# roco1044.net
KiCad netlist of a schematic drawn in EAGLE
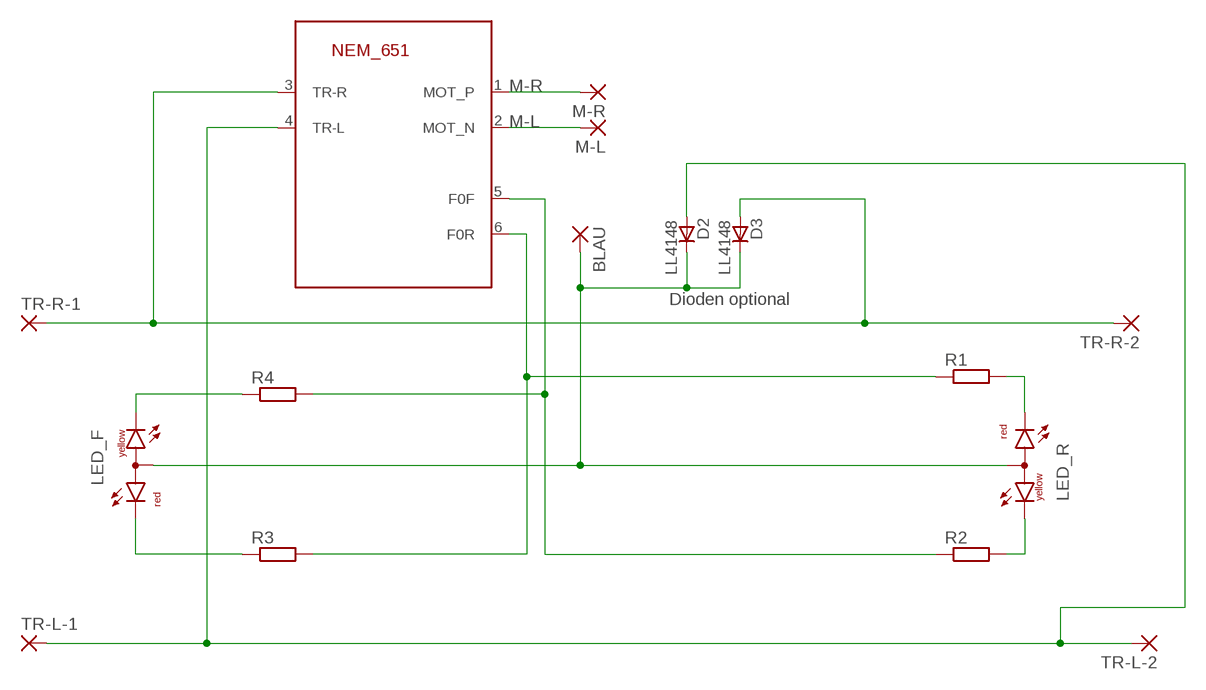
[diagram p0: schematic, sheet 1]

(export (version "E")
  (design (tool "Eeschema 10.0.6"))
  (components
    (comp (ref "651")
      (value "NEM_651-TS")
      (footprint "eagle-import:53047-06")
      (libsource (lib "eagle-import") (part "NEM_651-TS"))
    )
    (comp (ref "BLAU")
      (value "1,6/0,8")
      (footprint "eagle-import:1,6_0,8")
      (libsource (lib "eagle-import") (part "1,6/0,8"))
    )
    (comp (ref "D2")
      (value "LL4148")
      (footprint "eagle-import:SOD80_DO213AA_MINIMELF")
      (libsource (lib "eagle-import") (part "LL4148"))
    )
    (comp (ref "D3")
      (value "LL4148")
      (footprint "eagle-import:SOD80_DO213AA_MINIMELF")
      (libsource (lib "eagle-import") (part "LL4148"))
    )
    (comp (ref "LED_F")
      (value "DUOLED-RY-A")
      (footprint "eagle-import:DUOLED-A-5MM")
      (libsource (lib "eagle-import") (part "DUOLED-RY-A"))
    )
    (comp (ref "LED_R")
      (value "DUOLED-RY-A")
      (footprint "eagle-import:DUOLED-A-5MM")
      (libsource (lib "eagle-import") (part "DUOLED-RY-A"))
    )
    (comp (ref "M-L")
      (value "SMD5")
      (footprint "eagle-import:SMD2,54-5,08")
      (libsource (lib "eagle-import") (part "SMD5"))
    )
    (comp (ref "M-R")
      (value "SMD5")
      (footprint "eagle-import:SMD2,54-5,08")
      (libsource (lib "eagle-import") (part "SMD5"))
    )
    (comp (ref "R1")
      (value "R-EU_R1206")
      (footprint "eagle-import:R1206")
      (libsource (lib "eagle-import") (part "R-EU_R1206"))
    )
    (comp (ref "R2")
      (value "R-EU_R1206")
      (footprint "eagle-import:R1206")
      (libsource (lib "eagle-import") (part "R-EU_R1206"))
    )
    (comp (ref "R3")
      (value "R-EU_R1206")
      (footprint "eagle-import:R1206")
      (libsource (lib "eagle-import") (part "R-EU_R1206"))
    )
    (comp (ref "R4")
      (value "R-EU_R1206")
      (footprint "eagle-import:R1206")
      (libsource (lib "eagle-import") (part "R-EU_R1206"))
    )
    (comp (ref "TR-L-1")
      (value "SMD5")
      (footprint "eagle-import:SMD2,54-5,08")
      (libsource (lib "eagle-import") (part "SMD5"))
    )
    (comp (ref "TR-L-2")
      (value "SMD5")
      (footprint "eagle-import:SMD2,54-5,08")
      (libsource (lib "eagle-import") (part "SMD5"))
    )
    (comp (ref "TR-R-1")
      (value "SMD5")
      (footprint "eagle-import:SMD2,54-5,08")
      (libsource (lib "eagle-import") (part "SMD5"))
    )
    (comp (ref "TR-R-2")
      (value "SMD5")
      (footprint "eagle-import:SMD2,54-5,08")
      (libsource (lib "eagle-import") (part "SMD5"))
    )
  )
  (nets
    (net (code "1") (name "/M-L") (class "Default")
      (node (ref "651") (pin "2") (pinfunction "MOT_N_2") (pintype "bidirectional"))
      (node (ref "M-L") (pin "1") (pinfunction "P_1") (pintype "passive"))
    )
    (net (code "2") (name "/M-R") (class "Default")
      (node (ref "651") (pin "1") (pinfunction "MOT_P_1") (pintype "bidirectional"))
      (node (ref "M-R") (pin "1") (pinfunction "P_1") (pintype "passive"))
    )
    (net (code "3") (name "Net-(651-F0F)") (class "Default")
      (node (ref "651") (pin "5") (pinfunction "F0F_5") (pintype "bidirectional"))
      (node (ref "R2") (pin "1") (pinfunction "1_1") (pintype "passive"))
      (node (ref "R4") (pin "2") (pinfunction "2_2") (pintype "passive"))
    )
    (net (code "4") (name "Net-(651-F0R)") (class "Default")
      (node (ref "651") (pin "6") (pinfunction "F0R_6") (pintype "bidirectional"))
      (node (ref "R1") (pin "1") (pinfunction "1_1") (pintype "passive"))
      (node (ref "R3") (pin "2") (pinfunction "2_2") (pintype "passive"))
    )
    (net (code "5") (name "Net-(651-TR-L)") (class "Default")
      (node (ref "651") (pin "4") (pinfunction "TR-L_4") (pintype "bidirectional"))
      (node (ref "D2") (pin "A") (pinfunction "A_A") (pintype "passive"))
      (node (ref "TR-L-1") (pin "1") (pinfunction "P_1") (pintype "passive"))
      (node (ref "TR-L-2") (pin "1") (pinfunction "P_1") (pintype "passive"))
    )
    (net (code "6") (name "Net-(651-TR-R)") (class "Default")
      (node (ref "651") (pin "3") (pinfunction "TR-R_3") (pintype "bidirectional"))
      (node (ref "D3") (pin "A") (pinfunction "A_A") (pintype "passive"))
      (node (ref "TR-R-1") (pin "1") (pinfunction "P_1") (pintype "passive"))
      (node (ref "TR-R-2") (pin "1") (pinfunction "P_1") (pintype "passive"))
    )
    (net (code "7") (name "Net-(BLAU-P)") (class "Default")
      (node (ref "BLAU") (pin "1") (pinfunction "P_1") (pintype "passive"))
      (node (ref "D2") (pin "C") (pinfunction "C_C") (pintype "passive"))
      (node (ref "D3") (pin "C") (pinfunction "C_C") (pintype "passive"))
      (node (ref "LED_F") (pin "A") (pinfunction "A_A") (pintype "passive"))
      (node (ref "LED_R") (pin "A") (pinfunction "A_A") (pintype "passive"))
    )
    (net (code "8") (name "Net-(LED_F-CY)") (class "Default")
      (node (ref "LED_F") (pin "CX") (pinfunction "CY_CX") (pintype "passive"))
      (node (ref "R4") (pin "1") (pinfunction "1_1") (pintype "passive"))
    )
    (net (code "9") (name "Net-(LED_F-PadCR)") (class "Default")
      (node (ref "LED_F") (pin "CR") (pinfunction "CR_CR") (pintype "passive"))
      (node (ref "R3") (pin "1") (pinfunction "1_1") (pintype "passive"))
    )
    (net (code "10") (name "Net-(LED_R-CY)") (class "Default")
      (node (ref "LED_R") (pin "CX") (pinfunction "CY_CX") (pintype "passive"))
      (node (ref "R2") (pin "2") (pinfunction "2_2") (pintype "passive"))
    )
    (net (code "11") (name "Net-(LED_R-PadCR)") (class "Default")
      (node (ref "LED_R") (pin "CR") (pinfunction "CR_CR") (pintype "passive"))
      (node (ref "R1") (pin "2") (pinfunction "2_2") (pintype "passive"))
    )
  )
)
